# supply.net
KiCad netlist of a schematic drawn in Altium Designer
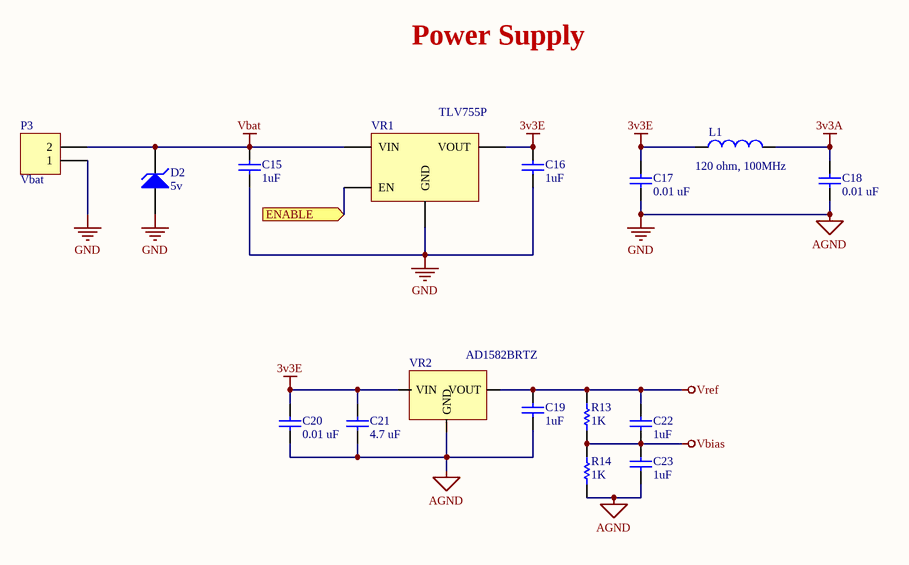
[diagram p0: supply.SchDoc]

(export (version "E")
  (design (tool "Eeschema 10.0.6"))
  (components
    (comp (ref "C15")
      (value "1uF")
      (footprint "Chip2PinWURTcap")
      (description "Ceramic Capacitors")
      (fields
        (field (name "MANUFACTURER") "Wurth Electronics")
        (field (name "MANUFACTURER PART NUMBER") "885012206052")
        (field (name "PUBLISHER") "Altium Limited")
      )
      (libsource (lib "lora_carrier") (part "885012206052"))
    )
    (comp (ref "C16")
      (value "1uF")
      (footprint "Chip2PinWURTcap")
      (description "Ceramic Capacitors")
      (fields
        (field (name "MANUFACTURER") "Wurth Electronics")
        (field (name "MANUFACTURER PART NUMBER") "885012206052")
        (field (name "PUBLISHER") "Altium Limited")
      )
      (libsource (lib "lora_carrier") (part "885012206052"))
    )
    (comp (ref "C17")
      (value "0.01 uF")
      (description "Multilayer Ceramic Capacitors MLCC - SMD/SMT WCAP-CSGP 0.01uF 0603 10% 50V MLCC")
      (fields
        (field (name "MANUFACTURER") "Wurth Electronics")
        (field (name "MANUFACTURER PART NUMBER") "885012206089")
      )
      (libsource (lib "lora_carrier") (part "885012206089"))
    )
    (comp (ref "C18")
      (value "0.01 uF")
      (description "Multilayer Ceramic Capacitors MLCC - SMD/SMT WCAP-CSGP 0.01uF 0603 10% 50V MLCC")
      (fields
        (field (name "MANUFACTURER") "Wurth Electronics")
        (field (name "MANUFACTURER PART NUMBER") "885012206089")
      )
      (libsource (lib "lora_carrier") (part "885012206089"))
    )
    (comp (ref "C19")
      (value "1uF")
      (footprint "Chip2PinWURTcap")
      (description "Ceramic Capacitors")
      (fields
        (field (name "MANUFACTURER") "Wurth Electronics")
        (field (name "MANUFACTURER PART NUMBER") "885012206052")
        (field (name "PUBLISHER") "Altium Limited")
      )
      (libsource (lib "lora_carrier") (part "885012206052"))
    )
    (comp (ref "C20")
      (value "0.01 uF")
      (description "Multilayer Ceramic Capacitors MLCC - SMD/SMT WCAP-CSGP 0.01uF 0603 10% 50V MLCC")
      (fields
        (field (name "MANUFACTURER") "Wurth Electronics")
        (field (name "MANUFACTURER PART NUMBER") "885012206089")
      )
      (libsource (lib "lora_carrier") (part "885012206089"))
    )
    (comp (ref "C21")
      (value "4.7 uF")
      (description "Multilayer Ceramic Capacitors MLCC - SMD/SMT FACTORY NOT ACCEPTING ORDERS")
      (fields (field (name "MANUFACTURER") "AVX") (field (name "MANUFACTURER PART NUMBER") "06036D475KAT2A"))
      (libsource (lib "lora_carrier") (part "06036D475KAT2A"))
    )
    (comp (ref "C22")
      (value "1uF")
      (footprint "Chip2PinWURTcap")
      (description "Ceramic Capacitors")
      (fields
        (field (name "MANUFACTURER") "Wurth Electronics")
        (field (name "MANUFACTURER PART NUMBER") "885012206052")
        (field (name "PUBLISHER") "Altium Limited")
      )
      (libsource (lib "lora_carrier") (part "885012206052"))
    )
    (comp (ref "C23")
      (value "1uF")
      (footprint "Chip2PinWURTcap")
      (description "Ceramic Capacitors")
      (fields
        (field (name "MANUFACTURER") "Wurth Electronics")
        (field (name "MANUFACTURER PART NUMBER") "885012206052")
        (field (name "PUBLISHER") "Altium Limited")
      )
      (libsource (lib "lora_carrier") (part "885012206052"))
    )
    (comp (ref "D2")
      (value "5v")
      (description "Zener Diodes 5-5.2V 5mA SOT-23; SOT-23")
      (fields
        (field (name "MANUFACTURER") "ROHM Semiconductor")
        (field (name "MANUFACTURER PART NUMBER") "BZX84B5V1LFHT116")
      )
      (libsource (lib "lora_carrier") (part "BZX84B5V1LFHT116"))
    )
    (comp (ref "L1")
      (value "120 ohm, 100MHz")
      (description "Ferrite Beads MULTILAYER CHIP BEAD Z=120 OHM@100MHz 25%")
      (fields
        (field (name "MANUFACTURER") "Fair-Rite")
        (field (name "MANUFACTURER PART NUMBER") "2506031217Z0")
      )
      (libsource (lib "lora_carrier") (part "2506031217Z0"))
    )
    (comp (ref "P3")
      (value "Vbat")
      (footprint "HDR1X2")
      (description "Header, 2-Pin")
      (fields (field (name "PUBLISHER") "Altium Limited"))
      (libsource (lib "Miscellaneous Connectors") (part "Header 2"))
    )
    (comp (ref "R13")
      (value "1K")
      (description "Thick Film Resistors - SMD 1/10Watt 1Kohms 1% Commercial Use")
      (fields
        (field (name "MANUFACTURER") "Vishay")
        (field (name "MANUFACTURER PART NUMBER") "CRCW06031K00FKEAC")
      )
      (libsource (lib "lora_carrier") (part "CRCW06031K00FKEAC"))
    )
    (comp (ref "R14")
      (value "1K")
      (description "Thick Film Resistors - SMD 1/10Watt 1Kohms 1% Commercial Use")
      (fields
        (field (name "MANUFACTURER") "Vishay")
        (field (name "MANUFACTURER PART NUMBER") "CRCW06031K00FKEAC")
      )
      (libsource (lib "lora_carrier") (part "CRCW06031K00FKEAC"))
    )
    (comp (ref "VR1")
      (value "TLV755P")
      (footprint "SOT23-TLV755P")
      (description "LDO Voltage Regulators 500-mA, Low IQ, Small Size, Low Dropout Regulator 5-SOT-23 -40 to 125")
      (fields
        (field (name "MANUFACTURER") "Texas Instruments")
        (field (name "MANUFACTURER PART NUMBER") "TLV75533PDBVR")
      )
      (libsource (lib "Schlib1") (part "TLV75533PDBVR"))
    )
    (comp (ref "VR2")
      (value "AD1582BRTZ")
      (description "Voltage References 2.5V MICROPOWER REF IC")
      (fields
        (field (name "MANUFACTURER") "Analog Devices")
        (field (name "MANUFACTURER PART NUMBER") "AD1582BRTZ-REEL7")
      )
      (libsource (lib "Schlib1") (part "AD1582BRTZ-REEL7"))
    )
  )
  (nets
    (net (code "1") (name "/ENABLE") (class "Default")
      (node (ref "VR1") (pin "3") (pinfunction "EN_3") (pintype "passive"))
    )
    (net (code "2") (name "3v3A") (class "Default")
      (node (ref "C18") (pin "1") (pinfunction "1_1") (pintype "passive"))
      (node (ref "L1") (pin "2") (pinfunction "2_2") (pintype "passive"))
    )
    (net (code "3") (name "3v3E") (class "Default")
      (node (ref "C16") (pin "1") (pinfunction "1_1") (pintype "passive"))
      (node (ref "C17") (pin "1") (pinfunction "1_1") (pintype "passive"))
      (node (ref "C20") (pin "2") (pinfunction "2_2") (pintype "passive"))
      (node (ref "C21") (pin "2") (pinfunction "2_2") (pintype "passive"))
      (node (ref "L1") (pin "1") (pinfunction "1_1") (pintype "passive"))
      (node (ref "VR1") (pin "5") (pinfunction "VOUT_5") (pintype "passive"))
      (node (ref "VR2") (pin "3") (pinfunction "VIN_3") (pintype "power_in"))
    )
    (net (code "4") (name "AGND") (class "Default")
      (node (ref "C15") (pin "2") (pinfunction "2_2") (pintype "passive"))
      (node (ref "C16") (pin "2") (pinfunction "2_2") (pintype "passive"))
      (node (ref "C17") (pin "2") (pinfunction "2_2") (pintype "passive"))
      (node (ref "C18") (pin "2") (pinfunction "2_2") (pintype "passive"))
      (node (ref "C19") (pin "1") (pinfunction "1_1") (pintype "passive"))
      (node (ref "C20") (pin "1") (pinfunction "1_1") (pintype "passive"))
      (node (ref "C21") (pin "1") (pinfunction "1_1") (pintype "passive"))
      (node (ref "C23") (pin "1") (pinfunction "1_1") (pintype "passive"))
      (node (ref "D2") (pin "1") (pinfunction "A_1") (pintype "passive"))
      (node (ref "P3") (pin "1") (pinfunction "1_1") (pintype "passive"))
      (node (ref "R14") (pin "2") (pinfunction "2_2") (pintype "passive"))
      (node (ref "VR1") (pin "2") (pinfunction "GND_2") (pintype "passive"))
      (node (ref "VR2") (pin "2") (pinfunction "GND_2") (pintype "power_in"))
    )
    (net (code "5") (name "Vbat") (class "Default")
      (node (ref "C15") (pin "1") (pinfunction "1_1") (pintype "passive"))
      (node (ref "D2") (pin "3") (pinfunction "K_3") (pintype "passive"))
      (node (ref "P3") (pin "2") (pinfunction "2_2") (pintype "passive"))
      (node (ref "VR1") (pin "1") (pinfunction "VIN_1") (pintype "passive"))
    )
    (net (code "6") (name "Vbias") (class "Default")
      (node (ref "C22") (pin "1") (pinfunction "1_1") (pintype "passive"))
      (node (ref "C23") (pin "2") (pinfunction "2_2") (pintype "passive"))
      (node (ref "R13") (pin "2") (pinfunction "2_2") (pintype "passive"))
      (node (ref "R14") (pin "1") (pinfunction "1_1") (pintype "passive"))
    )
    (net (code "7") (name "Vref") (class "Default")
      (node (ref "C19") (pin "2") (pinfunction "2_2") (pintype "passive"))
      (node (ref "C22") (pin "2") (pinfunction "2_2") (pintype "passive"))
      (node (ref "R13") (pin "1") (pinfunction "1_1") (pintype "passive"))
      (node (ref "VR2") (pin "1") (pinfunction "VOUT_1") (pintype "power_in"))
    )
  )
)
